# chess_module_LEDs.net
KiCad netlist of a schematic drawn in Altium Designer
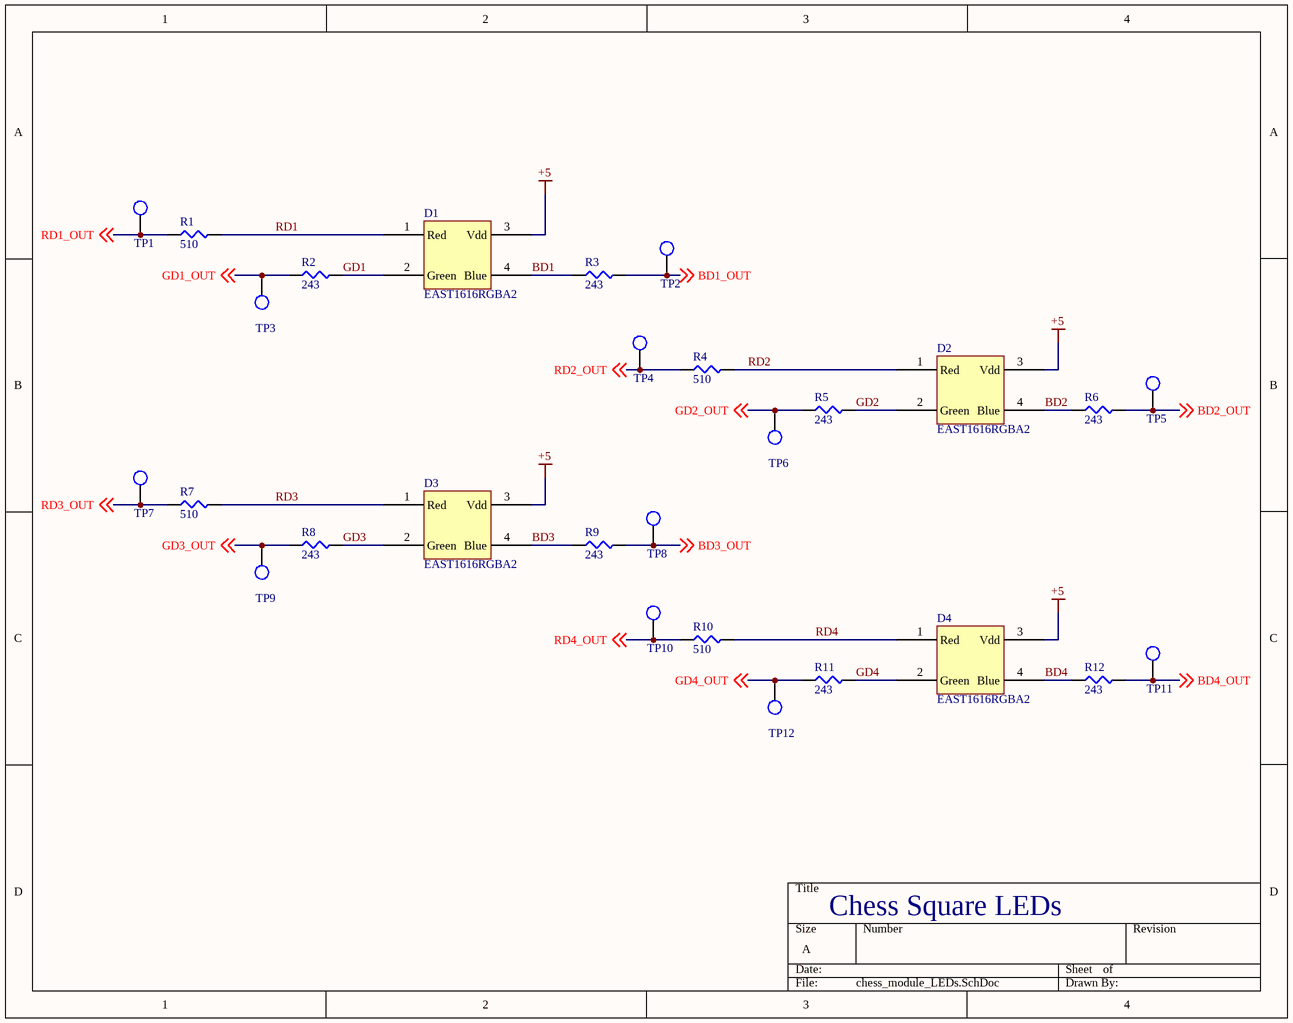
[diagram p0: chess_module_LEDs.SchDoc]

(export (version "E")
  (design (tool "Eeschema 10.0.6"))
  (components
    (comp (ref "D1")
      (value "EAST1616RGBA2")
      (footprint "EAST1616RGBA2")
      (libsource (lib "chess_module") (part "EAST1616RGBA2"))
    )
    (comp (ref "D2")
      (value "EAST1616RGBA2")
      (footprint "EAST1616RGBA2")
      (libsource (lib "chess_module") (part "EAST1616RGBA2"))
    )
    (comp (ref "D3")
      (value "EAST1616RGBA2")
      (footprint "EAST1616RGBA2")
      (libsource (lib "chess_module") (part "EAST1616RGBA2"))
    )
    (comp (ref "D4")
      (value "EAST1616RGBA2")
      (footprint "EAST1616RGBA2")
      (libsource (lib "chess_module") (part "EAST1616RGBA2"))
    )
    (comp (ref "R1")
      (value "510")
      (footprint "SMD-0805-RES")
      (description "RES SMD 510 OHM 1% 1/8W 0805")
      (fields (field (name "PART NUMBER") "ERJ-6ENF5100V") (field (name "DIGI-KEY PART NUMBER") "P510CCT-ND"))
      (libsource (lib "chess_module") (part "ERJ-6ENF5100V"))
    )
    (comp (ref "R2")
      (value "243")
      (footprint "SMD-0805-RES")
      (description "RES SMD 243 OHM 1% 1/8W 0805")
      (fields (field (name "PART NUMBER") "ERJ-6ENF2430V") (field (name "DIGI-KEY PART NUMBER") "P243CCT-ND"))
      (libsource (lib "chess_module") (part "ERJ-6ENF2430V"))
    )
    (comp (ref "R3")
      (value "243")
      (footprint "SMD-0805-RES")
      (description "RES SMD 243 OHM 1% 1/8W 0805")
      (fields (field (name "PART NUMBER") "ERJ-6ENF2430V") (field (name "DIGI-KEY PART NUMBER") "P243CCT-ND"))
      (libsource (lib "chess_module") (part "ERJ-6ENF2430V"))
    )
    (comp (ref "R4")
      (value "510")
      (footprint "SMD-0805-RES")
      (description "RES SMD 510 OHM 1% 1/8W 0805")
      (fields (field (name "PART NUMBER") "ERJ-6ENF5100V") (field (name "DIGI-KEY PART NUMBER") "P510CCT-ND"))
      (libsource (lib "chess_module") (part "ERJ-6ENF5100V"))
    )
    (comp (ref "R5")
      (value "243")
      (footprint "SMD-0805-RES")
      (description "RES SMD 243 OHM 1% 1/8W 0805")
      (fields (field (name "PART NUMBER") "ERJ-6ENF2430V") (field (name "DIGI-KEY PART NUMBER") "P243CCT-ND"))
      (libsource (lib "chess_module") (part "ERJ-6ENF2430V"))
    )
    (comp (ref "R6")
      (value "243")
      (footprint "SMD-0805-RES")
      (description "RES SMD 243 OHM 1% 1/8W 0805")
      (fields (field (name "PART NUMBER") "ERJ-6ENF2430V") (field (name "DIGI-KEY PART NUMBER") "P243CCT-ND"))
      (libsource (lib "chess_module") (part "ERJ-6ENF2430V"))
    )
    (comp (ref "R7")
      (value "510")
      (footprint "SMD-0805-RES")
      (description "RES SMD 510 OHM 1% 1/8W 0805")
      (fields (field (name "PART NUMBER") "ERJ-6ENF5100V") (field (name "DIGI-KEY PART NUMBER") "P510CCT-ND"))
      (libsource (lib "chess_module") (part "ERJ-6ENF5100V"))
    )
    (comp (ref "R8")
      (value "243")
      (footprint "SMD-0805-RES")
      (description "RES SMD 243 OHM 1% 1/8W 0805")
      (fields (field (name "PART NUMBER") "ERJ-6ENF2430V") (field (name "DIGI-KEY PART NUMBER") "P243CCT-ND"))
      (libsource (lib "chess_module") (part "ERJ-6ENF2430V"))
    )
    (comp (ref "R9")
      (value "243")
      (footprint "SMD-0805-RES")
      (description "RES SMD 243 OHM 1% 1/8W 0805")
      (fields (field (name "PART NUMBER") "ERJ-6ENF2430V") (field (name "DIGI-KEY PART NUMBER") "P243CCT-ND"))
      (libsource (lib "chess_module") (part "ERJ-6ENF2430V"))
    )
    (comp (ref "R10")
      (value "510")
      (footprint "SMD-0805-RES")
      (description "RES SMD 510 OHM 1% 1/8W 0805")
      (fields (field (name "PART NUMBER") "ERJ-6ENF5100V") (field (name "DIGI-KEY PART NUMBER") "P510CCT-ND"))
      (libsource (lib "chess_module") (part "ERJ-6ENF5100V"))
    )
    (comp (ref "R11")
      (value "243")
      (footprint "SMD-0805-RES")
      (description "RES SMD 243 OHM 1% 1/8W 0805")
      (fields (field (name "PART NUMBER") "ERJ-6ENF2430V") (field (name "DIGI-KEY PART NUMBER") "P243CCT-ND"))
      (libsource (lib "chess_module") (part "ERJ-6ENF2430V"))
    )
    (comp (ref "R12")
      (value "243")
      (footprint "SMD-0805-RES")
      (description "RES SMD 243 OHM 1% 1/8W 0805")
      (fields (field (name "PART NUMBER") "ERJ-6ENF2430V") (field (name "DIGI-KEY PART NUMBER") "P243CCT-ND"))
      (libsource (lib "chess_module") (part "ERJ-6ENF2430V"))
    )
    (comp (ref "TP1")
      (value "TP_1206")
      (footprint "TP-SMC-1206")
      (description "Test Point SMD 1206")
      (fields
        (field (name "MANUFACTURER") "TE Connectivity (Tyco Electronics)")
        (field (name "MANUFACTURER PART NUMBER") "1625854-1")
      )
      (libsource (lib "base-board") (part "TP_1206"))
    )
    (comp (ref "TP2")
      (value "TP_1206")
      (footprint "TP-SMC-1206")
      (description "Test Point SMD 1206")
      (fields
        (field (name "MANUFACTURER") "TE Connectivity (Tyco Electronics)")
        (field (name "MANUFACTURER PART NUMBER") "1625854-1")
      )
      (libsource (lib "base-board") (part "TP_1206"))
    )
    (comp (ref "TP3")
      (value "TP_1206")
      (footprint "TP-SMC-1206")
      (description "Test Point SMD 1206")
      (fields
        (field (name "MANUFACTURER") "TE Connectivity (Tyco Electronics)")
        (field (name "MANUFACTURER PART NUMBER") "1625854-1")
      )
      (libsource (lib "base-board") (part "TP_1206"))
    )
    (comp (ref "TP4")
      (value "TP_1206")
      (footprint "TP-SMC-1206")
      (description "Test Point SMD 1206")
      (fields
        (field (name "MANUFACTURER") "TE Connectivity (Tyco Electronics)")
        (field (name "MANUFACTURER PART NUMBER") "1625854-1")
      )
      (libsource (lib "base-board") (part "TP_1206"))
    )
    (comp (ref "TP5")
      (value "TP_1206")
      (footprint "TP-SMC-1206")
      (description "Test Point SMD 1206")
      (fields
        (field (name "MANUFACTURER") "TE Connectivity (Tyco Electronics)")
        (field (name "MANUFACTURER PART NUMBER") "1625854-1")
      )
      (libsource (lib "base-board") (part "TP_1206"))
    )
    (comp (ref "TP6")
      (value "TP_1206")
      (footprint "TP-SMC-1206")
      (description "Test Point SMD 1206")
      (fields
        (field (name "MANUFACTURER") "TE Connectivity (Tyco Electronics)")
        (field (name "MANUFACTURER PART NUMBER") "1625854-1")
      )
      (libsource (lib "base-board") (part "TP_1206"))
    )
    (comp (ref "TP7")
      (value "TP_1206")
      (footprint "TP-SMC-1206")
      (description "Test Point SMD 1206")
      (fields
        (field (name "MANUFACTURER") "TE Connectivity (Tyco Electronics)")
        (field (name "MANUFACTURER PART NUMBER") "1625854-1")
      )
      (libsource (lib "base-board") (part "TP_1206"))
    )
    (comp (ref "TP8")
      (value "TP_1206")
      (footprint "TP-SMC-1206")
      (description "Test Point SMD 1206")
      (fields
        (field (name "MANUFACTURER") "TE Connectivity (Tyco Electronics)")
        (field (name "MANUFACTURER PART NUMBER") "1625854-1")
      )
      (libsource (lib "base-board") (part "TP_1206"))
    )
    (comp (ref "TP9")
      (value "TP_1206")
      (footprint "TP-SMC-1206")
      (description "Test Point SMD 1206")
      (fields
        (field (name "MANUFACTURER") "TE Connectivity (Tyco Electronics)")
        (field (name "MANUFACTURER PART NUMBER") "1625854-1")
      )
      (libsource (lib "base-board") (part "TP_1206"))
    )
    (comp (ref "TP10")
      (value "TP_1206")
      (footprint "TP-SMC-1206")
      (description "Test Point SMD 1206")
      (fields
        (field (name "MANUFACTURER") "TE Connectivity (Tyco Electronics)")
        (field (name "MANUFACTURER PART NUMBER") "1625854-1")
      )
      (libsource (lib "base-board") (part "TP_1206"))
    )
    (comp (ref "TP11")
      (value "TP_1206")
      (footprint "TP-SMC-1206")
      (description "Test Point SMD 1206")
      (fields
        (field (name "MANUFACTURER") "TE Connectivity (Tyco Electronics)")
        (field (name "MANUFACTURER PART NUMBER") "1625854-1")
      )
      (libsource (lib "base-board") (part "TP_1206"))
    )
    (comp (ref "TP12")
      (value "TP_1206")
      (footprint "TP-SMC-1206")
      (description "Test Point SMD 1206")
      (fields
        (field (name "MANUFACTURER") "TE Connectivity (Tyco Electronics)")
        (field (name "MANUFACTURER PART NUMBER") "1625854-1")
      )
      (libsource (lib "base-board") (part "TP_1206"))
    )
  )
  (nets
    (net (code "1") (name "+5") (class "Default")
      (node (ref "D1") (pin "3") (pinfunction "Vdd_3") (pintype "passive"))
      (node (ref "D2") (pin "3") (pinfunction "Vdd_3") (pintype "passive"))
      (node (ref "D3") (pin "3") (pinfunction "Vdd_3") (pintype "passive"))
      (node (ref "D4") (pin "3") (pinfunction "Vdd_3") (pintype "passive"))
    )
    (net (code "2") (name "/BD1") (class "Default")
      (node (ref "D1") (pin "4") (pinfunction "Blue_4") (pintype "passive"))
      (node (ref "R3") (pin "1") (pinfunction "1_1") (pintype "passive"))
    )
    (net (code "3") (name "/BD2") (class "Default")
      (node (ref "D2") (pin "4") (pinfunction "Blue_4") (pintype "passive"))
      (node (ref "R6") (pin "1") (pinfunction "1_1") (pintype "passive"))
    )
    (net (code "4") (name "/BD3") (class "Default")
      (node (ref "D3") (pin "4") (pinfunction "Blue_4") (pintype "passive"))
      (node (ref "R9") (pin "1") (pinfunction "1_1") (pintype "passive"))
    )
    (net (code "5") (name "/BD4") (class "Default")
      (node (ref "D4") (pin "4") (pinfunction "Blue_4") (pintype "passive"))
      (node (ref "R12") (pin "1") (pinfunction "1_1") (pintype "passive"))
    )
    (net (code "6") (name "/GD1") (class "Default")
      (node (ref "D1") (pin "2") (pinfunction "Green_2") (pintype "passive"))
      (node (ref "R2") (pin "2") (pinfunction "2_2") (pintype "passive"))
    )
    (net (code "7") (name "/GD2") (class "Default")
      (node (ref "D2") (pin "2") (pinfunction "Green_2") (pintype "passive"))
      (node (ref "R5") (pin "2") (pinfunction "2_2") (pintype "passive"))
    )
    (net (code "8") (name "/GD3") (class "Default")
      (node (ref "D3") (pin "2") (pinfunction "Green_2") (pintype "passive"))
      (node (ref "R8") (pin "2") (pinfunction "2_2") (pintype "passive"))
    )
    (net (code "9") (name "/GD4") (class "Default")
      (node (ref "D4") (pin "2") (pinfunction "Green_2") (pintype "passive"))
      (node (ref "R11") (pin "2") (pinfunction "2_2") (pintype "passive"))
    )
    (net (code "10") (name "/RD1") (class "Default")
      (node (ref "D1") (pin "1") (pinfunction "Red_1") (pintype "passive"))
      (node (ref "R1") (pin "2") (pinfunction "2_2") (pintype "passive"))
    )
    (net (code "11") (name "/RD2") (class "Default")
      (node (ref "D2") (pin "1") (pinfunction "Red_1") (pintype "passive"))
      (node (ref "R4") (pin "2") (pinfunction "2_2") (pintype "passive"))
    )
    (net (code "12") (name "/RD3") (class "Default")
      (node (ref "D3") (pin "1") (pinfunction "Red_1") (pintype "passive"))
      (node (ref "R7") (pin "2") (pinfunction "2_2") (pintype "passive"))
    )
    (net (code "13") (name "/RD4") (class "Default")
      (node (ref "D4") (pin "1") (pinfunction "Red_1") (pintype "passive"))
      (node (ref "R10") (pin "2") (pinfunction "2_2") (pintype "passive"))
    )
    (net (code "14") (name "BD1_OUT") (class "Default")
      (node (ref "R3") (pin "2") (pinfunction "2_2") (pintype "passive"))
      (node (ref "TP2") (pin "1") (pintype "passive"))
    )
    (net (code "15") (name "BD2_OUT") (class "Default")
      (node (ref "R6") (pin "2") (pinfunction "2_2") (pintype "passive"))
      (node (ref "TP5") (pin "1") (pintype "passive"))
    )
    (net (code "16") (name "BD3_OUT") (class "Default")
      (node (ref "R9") (pin "2") (pinfunction "2_2") (pintype "passive"))
      (node (ref "TP8") (pin "1") (pintype "passive"))
    )
    (net (code "17") (name "BD4_OUT") (class "Default")
      (node (ref "R12") (pin "2") (pinfunction "2_2") (pintype "passive"))
      (node (ref "TP11") (pin "1") (pintype "passive"))
    )
    (net (code "18") (name "GD1_OUT") (class "Default")
      (node (ref "R2") (pin "1") (pinfunction "1_1") (pintype "passive"))
      (node (ref "TP3") (pin "1") (pintype "passive"))
    )
    (net (code "19") (name "GD2_OUT") (class "Default")
      (node (ref "R5") (pin "1") (pinfunction "1_1") (pintype "passive"))
      (node (ref "TP6") (pin "1") (pintype "passive"))
    )
    (net (code "20") (name "GD3_OUT") (class "Default")
      (node (ref "R8") (pin "1") (pinfunction "1_1") (pintype "passive"))
      (node (ref "TP9") (pin "1") (pintype "passive"))
    )
    (net (code "21") (name "GD4_OUT") (class "Default")
      (node (ref "R11") (pin "1") (pinfunction "1_1") (pintype "passive"))
      (node (ref "TP12") (pin "1") (pintype "passive"))
    )
    (net (code "22") (name "RD1_OUT") (class "Default")
      (node (ref "R1") (pin "1") (pinfunction "1_1") (pintype "passive"))
      (node (ref "TP1") (pin "1") (pintype "passive"))
    )
    (net (code "23") (name "RD2_OUT") (class "Default")
      (node (ref "R4") (pin "1") (pinfunction "1_1") (pintype "passive"))
      (node (ref "TP4") (pin "1") (pintype "passive"))
    )
    (net (code "24") (name "RD3_OUT") (class "Default")
      (node (ref "R7") (pin "1") (pinfunction "1_1") (pintype "passive"))
      (node (ref "TP7") (pin "1") (pintype "passive"))
    )
    (net (code "25") (name "RD4_OUT") (class "Default")
      (node (ref "R10") (pin "1") (pinfunction "1_1") (pintype "passive"))
      (node (ref "TP10") (pin "1") (pintype "passive"))
    )
  )
)
